# U_Disk.net
KiCad netlist of a schematic drawn in Altium Designer
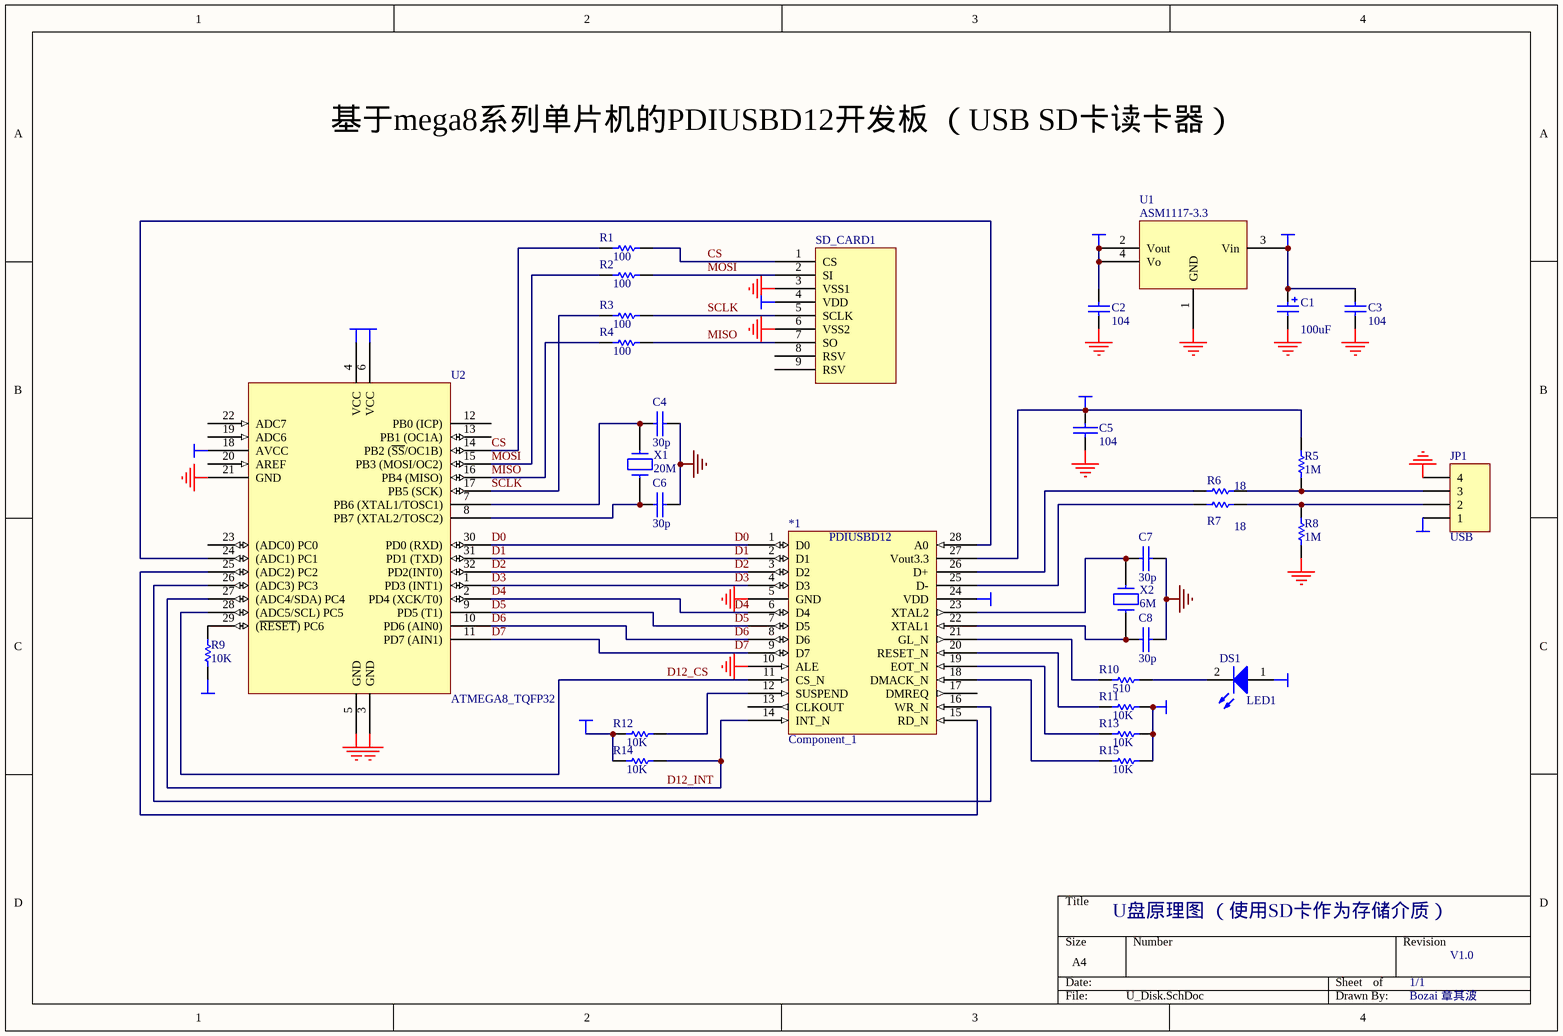
[diagram p0: U_Disk.SchDoc]

(export (version "E")
  (design (tool "Eeschema 10.0.6"))
  (components
    (comp (ref "*1") (value "Component_1") (libsource (lib "D12") (part "Component_1")))
    (comp (ref "C1")
      (value "Cap Pol1")
      (footprint "RB7.6-15")
      (description "Polarized Capacitor (Radial)")
      (fields
        (field (name "MANUFACTURER") "Generic Components")
        (field (name "ALTIUM_VALUE") "100uF")
        (field (name "PUBLISHER") "Altium Hobart Technology Centre")
      )
      (libsource (lib "Miscellaneous Devices") (part "Cap Pol1"))
    )
    (comp (ref "C2")
      (value "Cap")
      (footprint "RAD-0.3")
      (description "Capacitor")
      (fields
        (field (name "MANUFACTURER") "Generic Components")
        (field (name "ALTIUM_VALUE") "104")
        (field (name "PUBLISHER") "Altium Hobart Technology Centre")
      )
      (libsource (lib "Miscellaneous Devices") (part "Cap"))
    )
    (comp (ref "C3")
      (value "Cap")
      (footprint "RAD-0.3")
      (description "Capacitor")
      (fields
        (field (name "MANUFACTURER") "Generic Components")
        (field (name "ALTIUM_VALUE") "104")
        (field (name "PUBLISHER") "Altium Hobart Technology Centre")
      )
      (libsource (lib "Miscellaneous Devices") (part "Cap"))
    )
    (comp (ref "C4")
      (value "30p")
      (footprint "0805")
      (description "Capacitor")
      (libsource (lib "*") (part "CAP"))
    )
    (comp (ref "C5")
      (value "104")
      (footprint "0805")
      (description "Capacitor")
      (libsource (lib "*") (part "CAP"))
    )
    (comp (ref "C6")
      (value "30p")
      (footprint "0805")
      (description "Capacitor")
      (libsource (lib "*") (part "CAP"))
    )
    (comp (ref "C7")
      (value "30p")
      (footprint "0805")
      (description "Capacitor")
      (libsource (lib "*") (part "CAP"))
    )
    (comp (ref "C8")
      (value "30p")
      (footprint "0805")
      (description "Capacitor")
      (libsource (lib "*") (part "CAP"))
    )
    (comp (ref "DS1")
      (value "LED1")
      (footprint "LED-1")
      (description "Typical RED GaAs LED")
      (fields
        (field (name "MANUFACTURER") "Generic Components")
        (field (name "PUBLISHER") "Altium Hobart Technology Centre")
      )
      (libsource (lib "Miscellaneous Devices") (part "LED1"))
    )
    (comp (ref "JP1")
      (value "USB")
      (footprint "HDR1X4")
      (description "Header, 4-Pin")
      (fields (field (name "MANUFACTURER") "Generic Components"))
      (libsource (lib "Miscellaneous Connectors") (part "Header 4"))
    )
    (comp (ref "R1")
      (value "Res1")
      (footprint "AXIAL-0.3")
      (description "Resistor")
      (fields
        (field (name "MANUFACTURER") "Generic Components")
        (field (name "ALTIUM_VALUE") "100")
        (field (name "PUBLISHER") "Altium Hobart Technology Centre")
      )
      (libsource (lib "Miscellaneous Devices") (part "Res1"))
    )
    (comp (ref "R2")
      (value "Res1")
      (footprint "AXIAL-0.3")
      (description "Resistor")
      (fields
        (field (name "MANUFACTURER") "Generic Components")
        (field (name "ALTIUM_VALUE") "100")
        (field (name "PUBLISHER") "Altium Hobart Technology Centre")
      )
      (libsource (lib "Miscellaneous Devices") (part "Res1"))
    )
    (comp (ref "R3")
      (value "Res1")
      (footprint "AXIAL-0.3")
      (description "Resistor")
      (fields
        (field (name "MANUFACTURER") "Generic Components")
        (field (name "ALTIUM_VALUE") "100")
        (field (name "PUBLISHER") "Altium Hobart Technology Centre")
      )
      (libsource (lib "Miscellaneous Devices") (part "Res1"))
    )
    (comp (ref "R4")
      (value "Res1")
      (footprint "AXIAL-0.3")
      (description "Resistor")
      (fields
        (field (name "MANUFACTURER") "Generic Components")
        (field (name "ALTIUM_VALUE") "100")
        (field (name "PUBLISHER") "Altium Hobart Technology Centre")
      )
      (libsource (lib "Miscellaneous Devices") (part "Res1"))
    )
    (comp (ref "R5")
      (value "Res1")
      (footprint "AXIAL-0.3")
      (description "Resistor")
      (fields
        (field (name "MANUFACTURER") "Generic Components")
        (field (name "ALTIUM_VALUE") "1M")
        (field (name "PUBLISHER") "Altium Hobart Technology Centre")
      )
      (libsource (lib "Miscellaneous Devices") (part "Res1"))
    )
    (comp (ref "R6")
      (value "Res1")
      (footprint "AXIAL-0.3")
      (description "Resistor")
      (fields
        (field (name "MANUFACTURER") "Generic Components")
        (field (name "ALTIUM_VALUE") "18")
        (field (name "PUBLISHER") "Altium Hobart Technology Centre")
      )
      (libsource (lib "Miscellaneous Devices") (part "Res1"))
    )
    (comp (ref "R7")
      (value "Res1")
      (footprint "AXIAL-0.3")
      (description "Resistor")
      (fields
        (field (name "MANUFACTURER") "Generic Components")
        (field (name "ALTIUM_VALUE") "18")
        (field (name "PUBLISHER") "Altium Hobart Technology Centre")
      )
      (libsource (lib "Miscellaneous Devices") (part "Res1"))
    )
    (comp (ref "R8")
      (value "Res1")
      (footprint "AXIAL-0.3")
      (description "Resistor")
      (fields
        (field (name "MANUFACTURER") "Generic Components")
        (field (name "ALTIUM_VALUE") "1M")
        (field (name "PUBLISHER") "Altium Hobart Technology Centre")
      )
      (libsource (lib "Miscellaneous Devices") (part "Res1"))
    )
    (comp (ref "R9")
      (value "Res1")
      (footprint "AXIAL-0.3")
      (description "Resistor")
      (fields
        (field (name "MANUFACTURER") "Generic Components")
        (field (name "ALTIUM_VALUE") "10K")
        (field (name "PUBLISHER") "Altium Hobart Technology Centre")
      )
      (libsource (lib "Miscellaneous Devices") (part "Res1"))
    )
    (comp (ref "R10")
      (value "Res1")
      (footprint "AXIAL-0.3")
      (description "Resistor")
      (fields
        (field (name "MANUFACTURER") "Generic Components")
        (field (name "ALTIUM_VALUE") "510")
        (field (name "PUBLISHER") "Altium Hobart Technology Centre")
      )
      (libsource (lib "Miscellaneous Devices") (part "Res1"))
    )
    (comp (ref "R11")
      (value "Res1")
      (footprint "AXIAL-0.3")
      (description "Resistor")
      (fields
        (field (name "MANUFACTURER") "Generic Components")
        (field (name "ALTIUM_VALUE") "10K")
        (field (name "PUBLISHER") "Altium Hobart Technology Centre")
      )
      (libsource (lib "Miscellaneous Devices") (part "Res1"))
    )
    (comp (ref "R12")
      (value "Res1")
      (footprint "AXIAL-0.3")
      (description "Resistor")
      (fields
        (field (name "MANUFACTURER") "Generic Components")
        (field (name "ALTIUM_VALUE") "10K")
        (field (name "PUBLISHER") "Altium Hobart Technology Centre")
      )
      (libsource (lib "Miscellaneous Devices") (part "Res1"))
    )
    (comp (ref "R13")
      (value "Res1")
      (footprint "AXIAL-0.3")
      (description "Resistor")
      (fields
        (field (name "MANUFACTURER") "Generic Components")
        (field (name "ALTIUM_VALUE") "10K")
        (field (name "PUBLISHER") "Altium Hobart Technology Centre")
      )
      (libsource (lib "Miscellaneous Devices") (part "Res1"))
    )
    (comp (ref "R14")
      (value "Res1")
      (footprint "AXIAL-0.3")
      (description "Resistor")
      (fields
        (field (name "MANUFACTURER") "Generic Components")
        (field (name "ALTIUM_VALUE") "10K")
        (field (name "PUBLISHER") "Altium Hobart Technology Centre")
      )
      (libsource (lib "Miscellaneous Devices") (part "Res1"))
    )
    (comp (ref "R15")
      (value "Res1")
      (footprint "AXIAL-0.3")
      (description "Resistor")
      (fields
        (field (name "MANUFACTURER") "Generic Components")
        (field (name "ALTIUM_VALUE") "10K")
        (field (name "PUBLISHER") "Altium Hobart Technology Centre")
      )
      (libsource (lib "Miscellaneous Devices") (part "Res1"))
    )
    (comp (ref "SD_CARD1") (value "~") (footprint "SD_CON") (libsource (lib "*") (part "SD_SPI")))
    (comp (ref "U1") (value "ASM1117-3.3") (footprint "SOT223") (libsource (lib "*") (part "LM1084")))
    (comp (ref "U2")
      (value "ATMEGA8_TQFP32")
      (footprint "DIP-28")
      (description "Atmel Microcontroller - Library created by carel..  <www.mpfreezone.com>")
      (libsource (lib "AVR") (part "ATMEGA8_TQFP32"))
    )
    (comp (ref "X1")
      (value "20M")
      (footprint "CRYSTAL")
      (description "Crystal")
      (libsource (lib "*") (part "CRYSTAL"))
    )
    (comp (ref "X2")
      (value "6M")
      (footprint "CRYSTAL")
      (description "Crystal")
      (libsource (lib "*") (part "CRYSTAL"))
    )
  )
  (nets
    (net (code "1") (name "/CS") (class "Default")
      (node (ref "R1") (pin "1") (pinfunction "1_1") (pintype "passive"))
      (node (ref "R1") (pin "2") (pinfunction "2_2") (pintype "passive"))
      (node (ref "SD_CARD1") (pin "1") (pinfunction "CS_1") (pintype "passive"))
      (node (ref "U2") (pin "14") (pinfunction "PB2_(~{SS}/OC1B)_14") (pintype "bidirectional"))
    )
    (net (code "2") (name "/D0") (class "Default")
      (node (ref "*1") (pin "1") (pinfunction "D0_1") (pintype "bidirectional"))
      (node (ref "U2") (pin "30") (pinfunction "PD0_(RXD)_30") (pintype "bidirectional"))
    )
    (net (code "3") (name "/D1") (class "Default")
      (node (ref "*1") (pin "2") (pinfunction "D1_2") (pintype "bidirectional"))
      (node (ref "U2") (pin "31") (pinfunction "PD1_(TXD)_31") (pintype "bidirectional"))
    )
    (net (code "4") (name "/D2") (class "Default")
      (node (ref "*1") (pin "3") (pinfunction "D2_3") (pintype "bidirectional"))
      (node (ref "U2") (pin "32") (pinfunction "PD2(INT0)_32") (pintype "bidirectional"))
    )
    (net (code "5") (name "/D3") (class "Default")
      (node (ref "*1") (pin "4") (pinfunction "D3_4") (pintype "bidirectional"))
      (node (ref "U2") (pin "1") (pinfunction "PD3_(INT1)_1") (pintype "bidirectional"))
    )
    (net (code "6") (name "/D4") (class "Default")
      (node (ref "*1") (pin "6") (pinfunction "D4_6") (pintype "bidirectional"))
      (node (ref "U2") (pin "2") (pinfunction "PD4_(XCK/T0)_2") (pintype "bidirectional"))
    )
    (net (code "7") (name "/D5") (class "Default")
      (node (ref "*1") (pin "7") (pinfunction "D5_7") (pintype "bidirectional"))
      (node (ref "U2") (pin "9") (pinfunction "PD5_(T1)_9") (pintype "passive"))
    )
    (net (code "8") (name "/D6") (class "Default")
      (node (ref "*1") (pin "8") (pinfunction "D6_8") (pintype "bidirectional"))
      (node (ref "U2") (pin "10") (pinfunction "PD6_(AIN0)_10") (pintype "passive"))
    )
    (net (code "9") (name "/D7") (class "Default")
      (node (ref "*1") (pin "9") (pinfunction "D7_9") (pintype "bidirectional"))
      (node (ref "U2") (pin "11") (pinfunction "PD7_(AIN1)_11") (pintype "passive"))
    )
    (net (code "10") (name "/D12_CS") (class "Default")
      (node (ref "*1") (pin "11") (pinfunction "CS_N_11") (pintype "input"))
      (node (ref "U2") (pin "28") (pinfunction "(ADC5/SCL)_PC5_28") (pintype "bidirectional"))
    )
    (net (code "11") (name "/D12_INT") (class "Default")
      (node (ref "*1") (pin "14") (pinfunction "INT_N_14") (pintype "input"))
      (node (ref "R14") (pin "1") (pinfunction "1_1") (pintype "passive"))
      (node (ref "U2") (pin "27") (pinfunction "(ADC4/SDA)_PC4_27") (pintype "bidirectional"))
    )
    (net (code "12") (name "/MISO") (class "Default")
      (node (ref "R4") (pin "1") (pinfunction "1_1") (pintype "passive"))
      (node (ref "R4") (pin "2") (pinfunction "2_2") (pintype "passive"))
      (node (ref "SD_CARD1") (pin "7") (pinfunction "SO_7") (pintype "passive"))
      (node (ref "U2") (pin "16") (pinfunction "PB4_(MISO)_16") (pintype "bidirectional"))
    )
    (net (code "13") (name "/MOSI") (class "Default")
      (node (ref "R2") (pin "1") (pinfunction "1_1") (pintype "passive"))
      (node (ref "R2") (pin "2") (pinfunction "2_2") (pintype "passive"))
      (node (ref "SD_CARD1") (pin "2") (pinfunction "SI_2") (pintype "passive"))
      (node (ref "U2") (pin "15") (pinfunction "PB3_(MOSI/OC2)_15") (pintype "bidirectional"))
    )
    (net (code "14") (name "/SCLK") (class "Default")
      (node (ref "R3") (pin "1") (pinfunction "1_1") (pintype "passive"))
      (node (ref "R3") (pin "2") (pinfunction "2_2") (pintype "passive"))
      (node (ref "SD_CARD1") (pin "5") (pinfunction "SCLK_5") (pintype "passive"))
      (node (ref "U2") (pin "17") (pinfunction "PB5_(SCK)_17") (pintype "bidirectional"))
    )
    (net (code "15") (name "GND") (class "Default")
      (node (ref "*1") (pin "10") (pinfunction "ALE_10") (pintype "input"))
      (node (ref "*1") (pin "5") (pinfunction "GND_5") (pintype "power_in"))
      (node (ref "C1") (pin "2") (pinfunction "2_2") (pintype "passive"))
      (node (ref "C2") (pin "1") (pinfunction "1_1") (pintype "passive"))
      (node (ref "C3") (pin "1") (pinfunction "1_1") (pintype "passive"))
      (node (ref "C4") (pin "2") (pinfunction "2_2") (pintype "passive"))
      (node (ref "C5") (pin "1") (pinfunction "1_1") (pintype "passive"))
      (node (ref "C6") (pin "2") (pinfunction "2_2") (pintype "passive"))
      (node (ref "C7") (pin "2") (pinfunction "2_2") (pintype "passive"))
      (node (ref "C8") (pin "2") (pinfunction "2_2") (pintype "passive"))
      (node (ref "JP1") (pin "4") (pinfunction "4_4") (pintype "passive"))
      (node (ref "R8") (pin "2") (pinfunction "2_2") (pintype "passive"))
      (node (ref "SD_CARD1") (pin "3") (pinfunction "VSS1_3") (pintype "passive"))
      (node (ref "SD_CARD1") (pin "6") (pinfunction "VSS2_6") (pintype "passive"))
      (node (ref "U1") (pin "1") (pinfunction "GND_1") (pintype "passive"))
      (node (ref "U2") (pin "21") (pinfunction "GND_21") (pintype "passive"))
      (node (ref "U2") (pin "3") (pinfunction "GND_3") (pintype "passive"))
      (node (ref "U2") (pin "5") (pinfunction "GND_5") (pintype "power_in"))
    )
    (net (code "16") (name "Net-(*1-A0)") (class "Default")
      (node (ref "*1") (pin "28") (pinfunction "A0_28") (pintype "input"))
      (node (ref "U2") (pin "24") (pinfunction "(ADC1)_PC1_24") (pintype "bidirectional"))
    )
    (net (code "17") (name "Net-(*1-D+)") (class "Default")
      (node (ref "*1") (pin "26") (pinfunction "D+_26") (pintype "passive"))
      (node (ref "R6") (pin "1") (pinfunction "1_1") (pintype "passive"))
    )
    (net (code "18") (name "Net-(*1-D-)") (class "Default")
      (node (ref "*1") (pin "25") (pinfunction "D-_25") (pintype "passive"))
      (node (ref "R7") (pin "1") (pinfunction "1_1") (pintype "passive"))
    )
    (net (code "19") (name "Net-(*1-DMACK_N)") (class "Default")
      (node (ref "*1") (pin "18") (pinfunction "DMACK_N_18") (pintype "input"))
      (node (ref "R15") (pin "2") (pinfunction "2_2") (pintype "passive"))
    )
    (net (code "20") (name "Net-(*1-EOT_N)") (class "Default")
      (node (ref "*1") (pin "19") (pinfunction "EOT_N_19") (pintype "input"))
      (node (ref "R13") (pin "2") (pinfunction "2_2") (pintype "passive"))
    )
    (net (code "21") (name "Net-(*1-GL_N)") (class "Default")
      (node (ref "*1") (pin "21") (pinfunction "GL_N_21") (pintype "output"))
      (node (ref "R10") (pin "2") (pinfunction "2_2") (pintype "passive"))
    )
    (net (code "22") (name "Net-(*1-RD_N)") (class "Default")
      (node (ref "*1") (pin "15") (pinfunction "RD_N_15") (pintype "input"))
      (node (ref "U2") (pin "25") (pinfunction "(ADC2)_PC2_25") (pintype "bidirectional"))
    )
    (net (code "23") (name "Net-(*1-RESET_N)") (class "Default")
      (node (ref "*1") (pin "20") (pinfunction "RESET_N_20") (pintype "input"))
      (node (ref "R11") (pin "2") (pinfunction "2_2") (pintype "passive"))
    )
    (net (code "24") (name "Net-(*1-SUSPEND)") (class "Default")
      (node (ref "*1") (pin "12") (pinfunction "SUSPEND_12") (pintype "input"))
      (node (ref "R12") (pin "1") (pinfunction "1_1") (pintype "passive"))
    )
    (net (code "25") (name "Net-(*1-WR_N)") (class "Default")
      (node (ref "*1") (pin "16") (pinfunction "WR_N_16") (pintype "input"))
      (node (ref "U2") (pin "26") (pinfunction "(ADC3)_PC3_26") (pintype "bidirectional"))
    )
    (net (code "26") (name "Net-(*1-XTAL1)") (class "Default")
      (node (ref "*1") (pin "22") (pinfunction "XTAL1_22") (pintype "input"))
      (node (ref "C8") (pin "1") (pinfunction "1_1") (pintype "passive"))
      (node (ref "X2") (pin "2") (pinfunction "2_2") (pintype "passive"))
    )
    (net (code "27") (name "Net-(*1-XTAL2)") (class "Default")
      (node (ref "*1") (pin "23") (pinfunction "XTAL2_23") (pintype "output"))
      (node (ref "C7") (pin "1") (pinfunction "1_1") (pintype "passive"))
      (node (ref "X2") (pin "1") (pinfunction "1_1") (pintype "passive"))
    )
    (net (code "28") (name "Net-(DS1-K)") (class "Default")
      (node (ref "DS1") (pin "2") (pinfunction "K_2") (pintype "passive"))
      (node (ref "R10") (pin "1") (pinfunction "1_1") (pintype "passive"))
    )
    (net (code "29") (name "Net-(JP1-Pad2)") (class "Default")
      (node (ref "JP1") (pin "2") (pinfunction "2_2") (pintype "passive"))
      (node (ref "R7") (pin "2") (pinfunction "2_2") (pintype "passive"))
      (node (ref "R8") (pin "1") (pinfunction "1_1") (pintype "passive"))
    )
    (net (code "30") (name "Net-(JP1-Pad3)") (class "Default")
      (node (ref "JP1") (pin "3") (pinfunction "3_3") (pintype "passive"))
      (node (ref "R5") (pin "2") (pinfunction "2_2") (pintype "passive"))
      (node (ref "R6") (pin "2") (pinfunction "2_2") (pintype "passive"))
    )
    (net (code "31") (name "Net-(U2-(~{RESET})_PC6)") (class "Default")
      (node (ref "R9") (pin "1") (pinfunction "1_1") (pintype "passive"))
      (node (ref "U2") (pin "29") (pinfunction "(~{RESET})_PC6_29") (pintype "bidirectional"))
    )
    (net (code "32") (name "Net-(U2-PB6_(XTAL1{slash}TOSC1))") (class "Default")
      (node (ref "C4") (pin "1") (pinfunction "1_1") (pintype "passive"))
      (node (ref "U2") (pin "7") (pinfunction "PB6_(XTAL1/TOSC1)_7") (pintype "passive"))
      (node (ref "X1") (pin "1") (pinfunction "1_1") (pintype "passive"))
    )
    (net (code "33") (name "Net-(U2-PB7_(XTAL2{slash}TOSC2))") (class "Default")
      (node (ref "C6") (pin "1") (pinfunction "1_1") (pintype "passive"))
      (node (ref "U2") (pin "8") (pinfunction "PB7_(XTAL2/TOSC2)_8") (pintype "passive"))
      (node (ref "X1") (pin "2") (pinfunction "2_2") (pintype "passive"))
    )
    (net (code "34") (name "VCC") (class "Default")
      (node (ref "*1") (pin "24") (pinfunction "VDD_24") (pintype "power_in"))
      (node (ref "*1") (pin "27") (pinfunction "Vout3.3_27") (pintype "power_in"))
      (node (ref "C2") (pin "2") (pinfunction "2_2") (pintype "passive"))
      (node (ref "C5") (pin "2") (pinfunction "2_2") (pintype "passive"))
      (node (ref "DS1") (pin "1") (pinfunction "A_1") (pintype "passive"))
      (node (ref "R11") (pin "1") (pinfunction "1_1") (pintype "passive"))
      (node (ref "R12") (pin "2") (pinfunction "2_2") (pintype "passive"))
      (node (ref "R13") (pin "1") (pinfunction "1_1") (pintype "passive"))
      (node (ref "R14") (pin "2") (pinfunction "2_2") (pintype "passive"))
      (node (ref "R15") (pin "1") (pinfunction "1_1") (pintype "passive"))
      (node (ref "R5") (pin "1") (pinfunction "1_1") (pintype "passive"))
      (node (ref "R9") (pin "2") (pinfunction "2_2") (pintype "passive"))
      (node (ref "SD_CARD1") (pin "4") (pinfunction "VDD_4") (pintype "passive"))
      (node (ref "U1") (pin "2") (pinfunction "Vout_2") (pintype "passive"))
      (node (ref "U1") (pin "4") (pinfunction "Vo_4") (pintype "passive"))
      (node (ref "U2") (pin "18") (pinfunction "AVCC_18") (pintype "passive"))
      (node (ref "U2") (pin "4") (pinfunction "VCC_4") (pintype "power_in"))
      (node (ref "U2") (pin "6") (pinfunction "VCC_6") (pintype "passive"))
    )
    (net (code "35") (name "VCC_USB") (class "Default")
      (node (ref "C1") (pin "1") (pinfunction "1_1") (pintype "passive"))
      (node (ref "C3") (pin "2") (pinfunction "2_2") (pintype "passive"))
      (node (ref "JP1") (pin "1") (pinfunction "1_1") (pintype "passive"))
      (node (ref "U1") (pin "3") (pinfunction "Vin_3") (pintype "passive"))
    )
    (net (code "36") (name "unconnected-(*1-CLKOUT-Pad13)") (class "Default")
      (node (ref "*1") (pin "13") (pinfunction "CLKOUT_13") (pintype "output"))
    )
    (net (code "37") (name "unconnected-(*1-DMREQ-Pad17)") (class "Default")
      (node (ref "*1") (pin "17") (pinfunction "DMREQ_17") (pintype "output"))
    )
    (net (code "38") (name "unconnected-(SD_CARD1-RSV-Pad8)") (class "Default")
      (node (ref "SD_CARD1") (pin "8") (pinfunction "RSV_8") (pintype "passive"))
    )
    (net (code "39") (name "unconnected-(SD_CARD1-RSV-Pad9)") (class "Default")
      (node (ref "SD_CARD1") (pin "9") (pinfunction "RSV_9") (pintype "passive"))
    )
    (net (code "40") (name "unconnected-(U2-(ADC0)_PC0-Pad23)") (class "Default")
      (node (ref "U2") (pin "23") (pinfunction "(ADC0)_PC0_23") (pintype "bidirectional"))
    )
    (net (code "41") (name "unconnected-(U2-ADC6-Pad19)") (class "Default")
      (node (ref "U2") (pin "19") (pinfunction "ADC6_19") (pintype "input"))
    )
    (net (code "42") (name "unconnected-(U2-ADC7-Pad22)") (class "Default")
      (node (ref "U2") (pin "22") (pinfunction "ADC7_22") (pintype "input"))
    )
    (net (code "43") (name "unconnected-(U2-AREF-Pad20)") (class "Default")
      (node (ref "U2") (pin "20") (pinfunction "AREF_20") (pintype "input"))
    )
    (net (code "44") (name "unconnected-(U2-PB0_(ICP)-Pad12)") (class "Default")
      (node (ref "U2") (pin "12") (pinfunction "PB0_(ICP)_12") (pintype "passive"))
    )
    (net (code "45") (name "unconnected-(U2-PB1_(OC1A)-Pad13)") (class "Default")
      (node (ref "U2") (pin "13") (pinfunction "PB1_(OC1A)_13") (pintype "bidirectional"))
    )
  )
)
